# Sheet1.net
KiCad netlist of a schematic drawn in Altium Designer
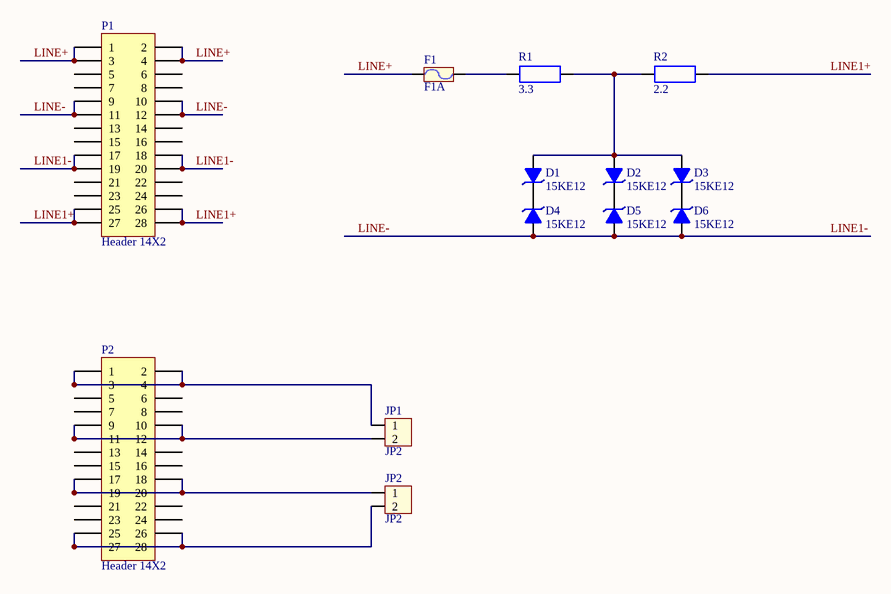
[diagram p0: Sheet1.SchDoc]

(export (version "E")
  (design (tool "Eeschema 10.0.6"))
  (components
    (comp (ref "D1") (value "15KE12") (footprint "D1A") (libsource (lib "Binh_BK") (part "Zener")))
    (comp (ref "D2") (value "15KE12") (footprint "D1A") (libsource (lib "Binh_BK") (part "Zener")))
    (comp (ref "D3") (value "15KE12") (footprint "D1A") (libsource (lib "Binh_BK") (part "Zener")))
    (comp (ref "D4") (value "15KE12") (footprint "D1A") (libsource (lib "Binh_BK") (part "Zener")))
    (comp (ref "D5") (value "15KE12") (footprint "D1A") (libsource (lib "Binh_BK") (part "Zener")))
    (comp (ref "D6") (value "15KE12") (footprint "D1A") (libsource (lib "Binh_BK") (part "Zener")))
    (comp (ref "F1")
      (value "F1A")
      (footprint "Fuse")
      (description "Fuse")
      (fields (field (name "DESIGNED BY") "VanDungEvn"))
      (libsource (lib "Binh_BK") (part "Fuse"))
    )
    (comp (ref "JP1")
      (value "JP2")
      (footprint "CON2")
      (description "Connector 2")
      (libsource (lib "Binh_BK") (part "Con2"))
    )
    (comp (ref "JP2")
      (value "JP2")
      (footprint "CON2")
      (description "Connector 2")
      (libsource (lib "Binh_BK") (part "Con2"))
    )
    (comp (ref "P1")
      (value "Header 14X2")
      (footprint "HDR2X14")
      (description "Header, 14-Pin, Dual row")
      (fields (field (name "PUBLISHER") "Altium Limited"))
      (libsource (lib "Miscellaneous Connectors") (part "Header 14X2"))
    )
    (comp (ref "P2")
      (value "Header 14X2")
      (footprint "HDR2X14")
      (description "Header, 14-Pin, Dual row")
      (fields (field (name "PUBLISHER") "Altium Limited"))
      (libsource (lib "Miscellaneous Connectors") (part "Header 14X2"))
    )
    (comp (ref "R1")
      (value "3.3")
      (footprint "R2W")
      (description "Resistor 2W")
      (libsource (lib "Binh_BK") (part "R2W"))
    )
    (comp (ref "R2")
      (value "2.2")
      (footprint "R2W")
      (description "Resistor 2W")
      (libsource (lib "Binh_BK") (part "R2W"))
    )
  )
  (nets
    (net (code "1") (name "/LINE+") (class "Default")
      (node (ref "F1") (pin "1") (pinfunction "1_1") (pintype "passive"))
      (node (ref "P1") (pin "1") (pinfunction "1_1") (pintype "passive"))
      (node (ref "P1") (pin "2") (pinfunction "2_2") (pintype "passive"))
      (node (ref "P1") (pin "3") (pinfunction "3_3") (pintype "passive"))
      (node (ref "P1") (pin "4") (pinfunction "4_4") (pintype "passive"))
    )
    (net (code "2") (name "/LINE-") (class "Default")
      (node (ref "D4") (pin "1") (pinfunction "A_1") (pintype "passive"))
      (node (ref "D5") (pin "1") (pinfunction "A_1") (pintype "passive"))
      (node (ref "D6") (pin "1") (pinfunction "A_1") (pintype "passive"))
      (node (ref "P1") (pin "10") (pinfunction "10_10") (pintype "passive"))
      (node (ref "P1") (pin "11") (pinfunction "11_11") (pintype "passive"))
      (node (ref "P1") (pin "12") (pinfunction "12_12") (pintype "passive"))
      (node (ref "P1") (pin "17") (pinfunction "17_17") (pintype "passive"))
      (node (ref "P1") (pin "18") (pinfunction "18_18") (pintype "passive"))
      (node (ref "P1") (pin "19") (pinfunction "19_19") (pintype "passive"))
      (node (ref "P1") (pin "20") (pinfunction "20_20") (pintype "passive"))
      (node (ref "P1") (pin "9") (pinfunction "9_9") (pintype "passive"))
    )
    (net (code "3") (name "/LINE1+") (class "Default")
      (node (ref "P1") (pin "25") (pinfunction "25_25") (pintype "passive"))
      (node (ref "P1") (pin "26") (pinfunction "26_26") (pintype "passive"))
      (node (ref "P1") (pin "27") (pinfunction "27_27") (pintype "passive"))
      (node (ref "P1") (pin "28") (pinfunction "28_28") (pintype "passive"))
      (node (ref "R2") (pin "2") (pinfunction "2_2") (pintype "passive"))
    )
    (net (code "4") (name "Net-(D1-A)") (class "Default")
      (node (ref "D1") (pin "1") (pinfunction "A_1") (pintype "passive"))
      (node (ref "D2") (pin "1") (pinfunction "A_1") (pintype "passive"))
      (node (ref "D3") (pin "1") (pinfunction "A_1") (pintype "passive"))
      (node (ref "R1") (pin "2") (pinfunction "2_2") (pintype "passive"))
      (node (ref "R2") (pin "1") (pinfunction "1_1") (pintype "passive"))
    )
    (net (code "5") (name "Net-(D1-K)") (class "Default")
      (node (ref "D1") (pin "2") (pinfunction "K_2") (pintype "passive"))
      (node (ref "D4") (pin "2") (pinfunction "K_2") (pintype "passive"))
    )
    (net (code "6") (name "Net-(D2-K)") (class "Default")
      (node (ref "D2") (pin "2") (pinfunction "K_2") (pintype "passive"))
      (node (ref "D5") (pin "2") (pinfunction "K_2") (pintype "passive"))
    )
    (net (code "7") (name "Net-(D3-K)") (class "Default")
      (node (ref "D3") (pin "2") (pinfunction "K_2") (pintype "passive"))
      (node (ref "D6") (pin "2") (pinfunction "K_2") (pintype "passive"))
    )
    (net (code "8") (name "Net-(F1-Pad2)") (class "Default")
      (node (ref "F1") (pin "2") (pinfunction "2_2") (pintype "passive"))
      (node (ref "R1") (pin "1") (pinfunction "1_1") (pintype "passive"))
    )
    (net (code "9") (name "Net-(JP1-Pad1)") (class "Default")
      (node (ref "JP1") (pin "1") (pinfunction "1_1") (pintype "passive"))
      (node (ref "P2") (pin "1") (pinfunction "1_1") (pintype "passive"))
      (node (ref "P2") (pin "2") (pinfunction "2_2") (pintype "passive"))
      (node (ref "P2") (pin "3") (pinfunction "3_3") (pintype "passive"))
      (node (ref "P2") (pin "4") (pinfunction "4_4") (pintype "passive"))
    )
    (net (code "10") (name "Net-(JP1-Pad2)") (class "Default")
      (node (ref "JP1") (pin "2") (pinfunction "2_2") (pintype "passive"))
      (node (ref "P2") (pin "10") (pinfunction "10_10") (pintype "passive"))
      (node (ref "P2") (pin "11") (pinfunction "11_11") (pintype "passive"))
      (node (ref "P2") (pin "12") (pinfunction "12_12") (pintype "passive"))
      (node (ref "P2") (pin "9") (pinfunction "9_9") (pintype "passive"))
    )
    (net (code "11") (name "Net-(JP2-Pad1)") (class "Default")
      (node (ref "JP2") (pin "1") (pinfunction "1_1") (pintype "passive"))
      (node (ref "P2") (pin "17") (pinfunction "17_17") (pintype "passive"))
      (node (ref "P2") (pin "18") (pinfunction "18_18") (pintype "passive"))
      (node (ref "P2") (pin "19") (pinfunction "19_19") (pintype "passive"))
      (node (ref "P2") (pin "20") (pinfunction "20_20") (pintype "passive"))
    )
    (net (code "12") (name "Net-(JP2-Pad2)") (class "Default")
      (node (ref "JP2") (pin "2") (pinfunction "2_2") (pintype "passive"))
      (node (ref "P2") (pin "25") (pinfunction "25_25") (pintype "passive"))
      (node (ref "P2") (pin "26") (pinfunction "26_26") (pintype "passive"))
      (node (ref "P2") (pin "27") (pinfunction "27_27") (pintype "passive"))
      (node (ref "P2") (pin "28") (pinfunction "28_28") (pintype "passive"))
    )
    (net (code "13") (name "unconnected-(P1-Pad5)") (class "Default")
      (node (ref "P1") (pin "5") (pinfunction "5_5") (pintype "passive"))
    )
    (net (code "14") (name "unconnected-(P1-Pad6)") (class "Default")
      (node (ref "P1") (pin "6") (pinfunction "6_6") (pintype "passive"))
    )
    (net (code "15") (name "unconnected-(P1-Pad7)") (class "Default")
      (node (ref "P1") (pin "7") (pinfunction "7_7") (pintype "passive"))
    )
    (net (code "16") (name "unconnected-(P1-Pad8)") (class "Default")
      (node (ref "P1") (pin "8") (pinfunction "8_8") (pintype "passive"))
    )
    (net (code "17") (name "unconnected-(P1-Pad13)") (class "Default")
      (node (ref "P1") (pin "13") (pinfunction "13_13") (pintype "passive"))
    )
    (net (code "18") (name "unconnected-(P1-Pad14)") (class "Default")
      (node (ref "P1") (pin "14") (pinfunction "14_14") (pintype "passive"))
    )
    (net (code "19") (name "unconnected-(P1-Pad15)") (class "Default")
      (node (ref "P1") (pin "15") (pinfunction "15_15") (pintype "passive"))
    )
    (net (code "20") (name "unconnected-(P1-Pad16)") (class "Default")
      (node (ref "P1") (pin "16") (pinfunction "16_16") (pintype "passive"))
    )
    (net (code "21") (name "unconnected-(P1-Pad21)") (class "Default")
      (node (ref "P1") (pin "21") (pinfunction "21_21") (pintype "passive"))
    )
    (net (code "22") (name "unconnected-(P1-Pad22)") (class "Default")
      (node (ref "P1") (pin "22") (pinfunction "22_22") (pintype "passive"))
    )
    (net (code "23") (name "unconnected-(P1-Pad23)") (class "Default")
      (node (ref "P1") (pin "23") (pinfunction "23_23") (pintype "passive"))
    )
    (net (code "24") (name "unconnected-(P1-Pad24)") (class "Default")
      (node (ref "P1") (pin "24") (pinfunction "24_24") (pintype "passive"))
    )
    (net (code "25") (name "unconnected-(P2-Pad5)") (class "Default")
      (node (ref "P2") (pin "5") (pinfunction "5_5") (pintype "passive"))
    )
    (net (code "26") (name "unconnected-(P2-Pad6)") (class "Default")
      (node (ref "P2") (pin "6") (pinfunction "6_6") (pintype "passive"))
    )
    (net (code "27") (name "unconnected-(P2-Pad7)") (class "Default")
      (node (ref "P2") (pin "7") (pinfunction "7_7") (pintype "passive"))
    )
    (net (code "28") (name "unconnected-(P2-Pad8)") (class "Default")
      (node (ref "P2") (pin "8") (pinfunction "8_8") (pintype "passive"))
    )
    (net (code "29") (name "unconnected-(P2-Pad13)") (class "Default")
      (node (ref "P2") (pin "13") (pinfunction "13_13") (pintype "passive"))
    )
    (net (code "30") (name "unconnected-(P2-Pad14)") (class "Default")
      (node (ref "P2") (pin "14") (pinfunction "14_14") (pintype "passive"))
    )
    (net (code "31") (name "unconnected-(P2-Pad15)") (class "Default")
      (node (ref "P2") (pin "15") (pinfunction "15_15") (pintype "passive"))
    )
    (net (code "32") (name "unconnected-(P2-Pad16)") (class "Default")
      (node (ref "P2") (pin "16") (pinfunction "16_16") (pintype "passive"))
    )
    (net (code "33") (name "unconnected-(P2-Pad21)") (class "Default")
      (node (ref "P2") (pin "21") (pinfunction "21_21") (pintype "passive"))
    )
    (net (code "34") (name "unconnected-(P2-Pad22)") (class "Default")
      (node (ref "P2") (pin "22") (pinfunction "22_22") (pintype "passive"))
    )
    (net (code "35") (name "unconnected-(P2-Pad23)") (class "Default")
      (node (ref "P2") (pin "23") (pinfunction "23_23") (pintype "passive"))
    )
    (net (code "36") (name "unconnected-(P2-Pad24)") (class "Default")
      (node (ref "P2") (pin "24") (pinfunction "24_24") (pintype "passive"))
    )
  )
)
